# ICSP.net
KiCad netlist of a schematic drawn in Altium Designer
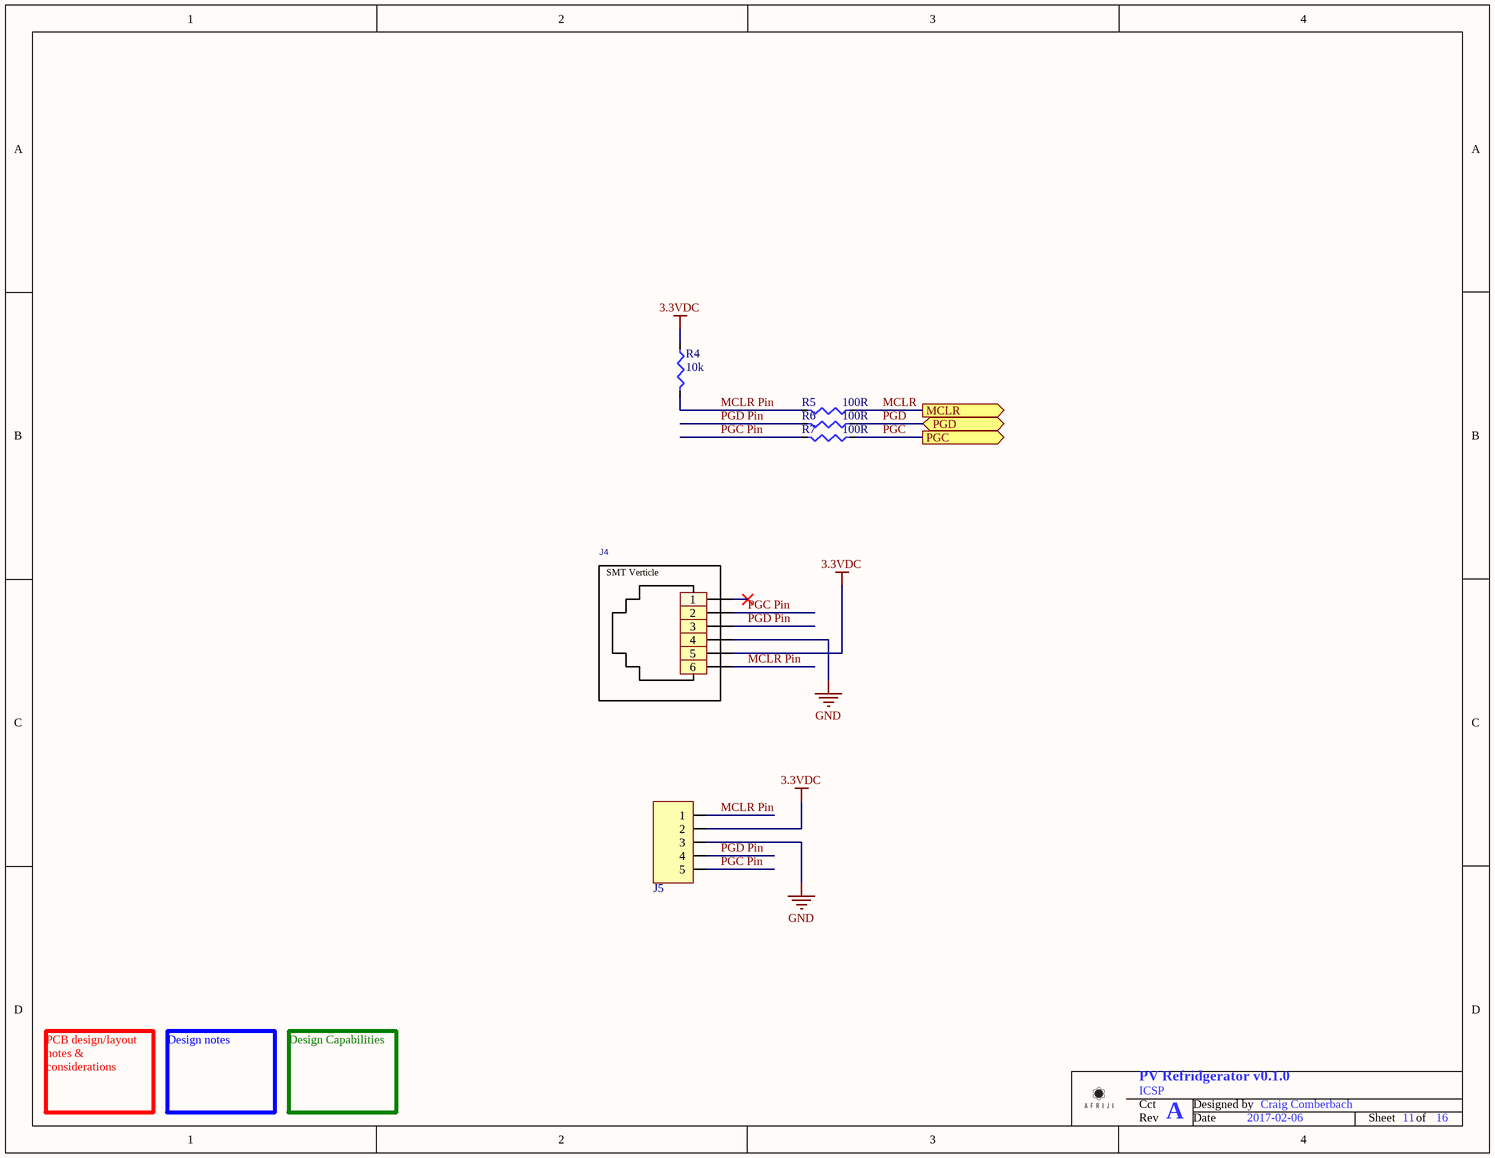
[diagram p0: ICSP.SchDoc]

(export (version "E")
  (design (tool "Eeschema 10.0.6"))
  (components
    (comp (ref "J4")
      (value "RJ12 Verticle SMT")
      (footprint "Connector- RJ12 Vertical SMT")
      (fields
        (field (name "MANUFACTURER") "Molex Inc")
        (field (name "MANUFACTURER PART NUMBER") "0855135114")
      )
      (libsource (lib "Integrated Component Library") (part "RJ12 Verticle SMT"))
    )
    (comp (ref "J5")
      (value "MTA100 - 5-Pin with friction Lock")
      (footprint "Connector - MTA-100 5 Position")
      (description "Flash Programmer")
      (fields
        (field (name "MANUFACTURER") "TE Connectivity")
        (field (name "MANUFACTURER PART NUMBER") "640456-5")
      )
      (libsource (lib "Integrated Component Library") (part "MTA100 - 5-Pin with friction Lock"))
    )
    (comp (ref "R4")
      (value "10k 0603 1%")
      (footprint "R0603")
      (description "Resistor")
      (fields
        (field (name "MANUFACTURER") "Yageo")
        (field (name "MANUFACTURER PART NUMBER") "RC0603FR-0710KL")
        (field (name "RESISTANCE (OHMS)") "10k")
      )
      (libsource (lib "Personal Library") (part "10k 0603 1%"))
    )
    (comp (ref "R5")
      (value "100R 0603 1%")
      (footprint "R0603")
      (description "1/8W")
      (fields
        (field (name "MANUFACTURER") "Yageo")
        (field (name "MANUFACTURER PART NUMBER") "RC0603FR-07100RL")
        (field (name "RESISTANCE (OHMS)") "100R")
      )
      (libsource (lib "Personal Library") (part "100R 0603 1%"))
    )
    (comp (ref "R6")
      (value "100R 0603 1%")
      (footprint "R0603")
      (description "1/8W")
      (fields
        (field (name "MANUFACTURER") "Yageo")
        (field (name "MANUFACTURER PART NUMBER") "RC0603FR-07100RL")
        (field (name "RESISTANCE (OHMS)") "100R")
      )
      (libsource (lib "Personal Library") (part "100R 0603 1%"))
    )
    (comp (ref "R7")
      (value "100R 0603 1%")
      (footprint "R0603")
      (description "1/8W")
      (fields
        (field (name "MANUFACTURER") "Yageo")
        (field (name "MANUFACTURER PART NUMBER") "RC0603FR-07100RL")
        (field (name "RESISTANCE (OHMS)") "100R")
      )
      (libsource (lib "Personal Library") (part "100R 0603 1%"))
    )
  )
  (nets
    (net (code "1") (name "/MCLR") (class "Default")
      (node (ref "R5") (pin "2") (pinfunction "2_2") (pintype "passive"))
    )
    (net (code "2") (name "/MCLR Pin") (class "Default")
      (node (ref "J4") (pin "6") (pinfunction "6_6") (pintype "passive"))
      (node (ref "J5") (pin "1") (pinfunction "1_1") (pintype "passive"))
      (node (ref "R4") (pin "2") (pinfunction "2_2") (pintype "passive"))
      (node (ref "R5") (pin "1") (pinfunction "1_1") (pintype "passive"))
    )
    (net (code "3") (name "/PGC") (class "Default")
      (node (ref "R7") (pin "2") (pinfunction "2_2") (pintype "passive"))
    )
    (net (code "4") (name "/PGC Pin") (class "Default")
      (node (ref "J4") (pin "2") (pinfunction "2_2") (pintype "passive"))
      (node (ref "J5") (pin "5") (pinfunction "5_5") (pintype "passive"))
      (node (ref "R7") (pin "1") (pinfunction "1_1") (pintype "passive"))
    )
    (net (code "5") (name "/PGD") (class "Default")
      (node (ref "R6") (pin "2") (pinfunction "2_2") (pintype "passive"))
    )
    (net (code "6") (name "/PGD Pin") (class "Default")
      (node (ref "J4") (pin "3") (pinfunction "3_3") (pintype "passive"))
      (node (ref "J5") (pin "4") (pinfunction "4_4") (pintype "passive"))
      (node (ref "R6") (pin "1") (pinfunction "1_1") (pintype "passive"))
    )
    (net (code "7") (name "3.3VDC") (class "Default")
      (node (ref "J4") (pin "5") (pinfunction "5_5") (pintype "passive"))
      (node (ref "J5") (pin "2") (pinfunction "2_2") (pintype "passive"))
      (node (ref "R4") (pin "1") (pinfunction "1_1") (pintype "passive"))
    )
    (net (code "8") (name "GND") (class "Default")
      (node (ref "J4") (pin "4") (pinfunction "4_4") (pintype "passive"))
      (node (ref "J5") (pin "3") (pinfunction "3_3") (pintype "passive"))
    )
    (net (code "9") (name "unconnected-(J4-Pad1)") (class "Default")
      (node (ref "J4") (pin "1") (pinfunction "1_1") (pintype "passive+no_connect"))
    )
  )
)
